# SimulatorT1-T2-AdapterRevB.net
KiCad netlist of a schematic drawn in EAGLE
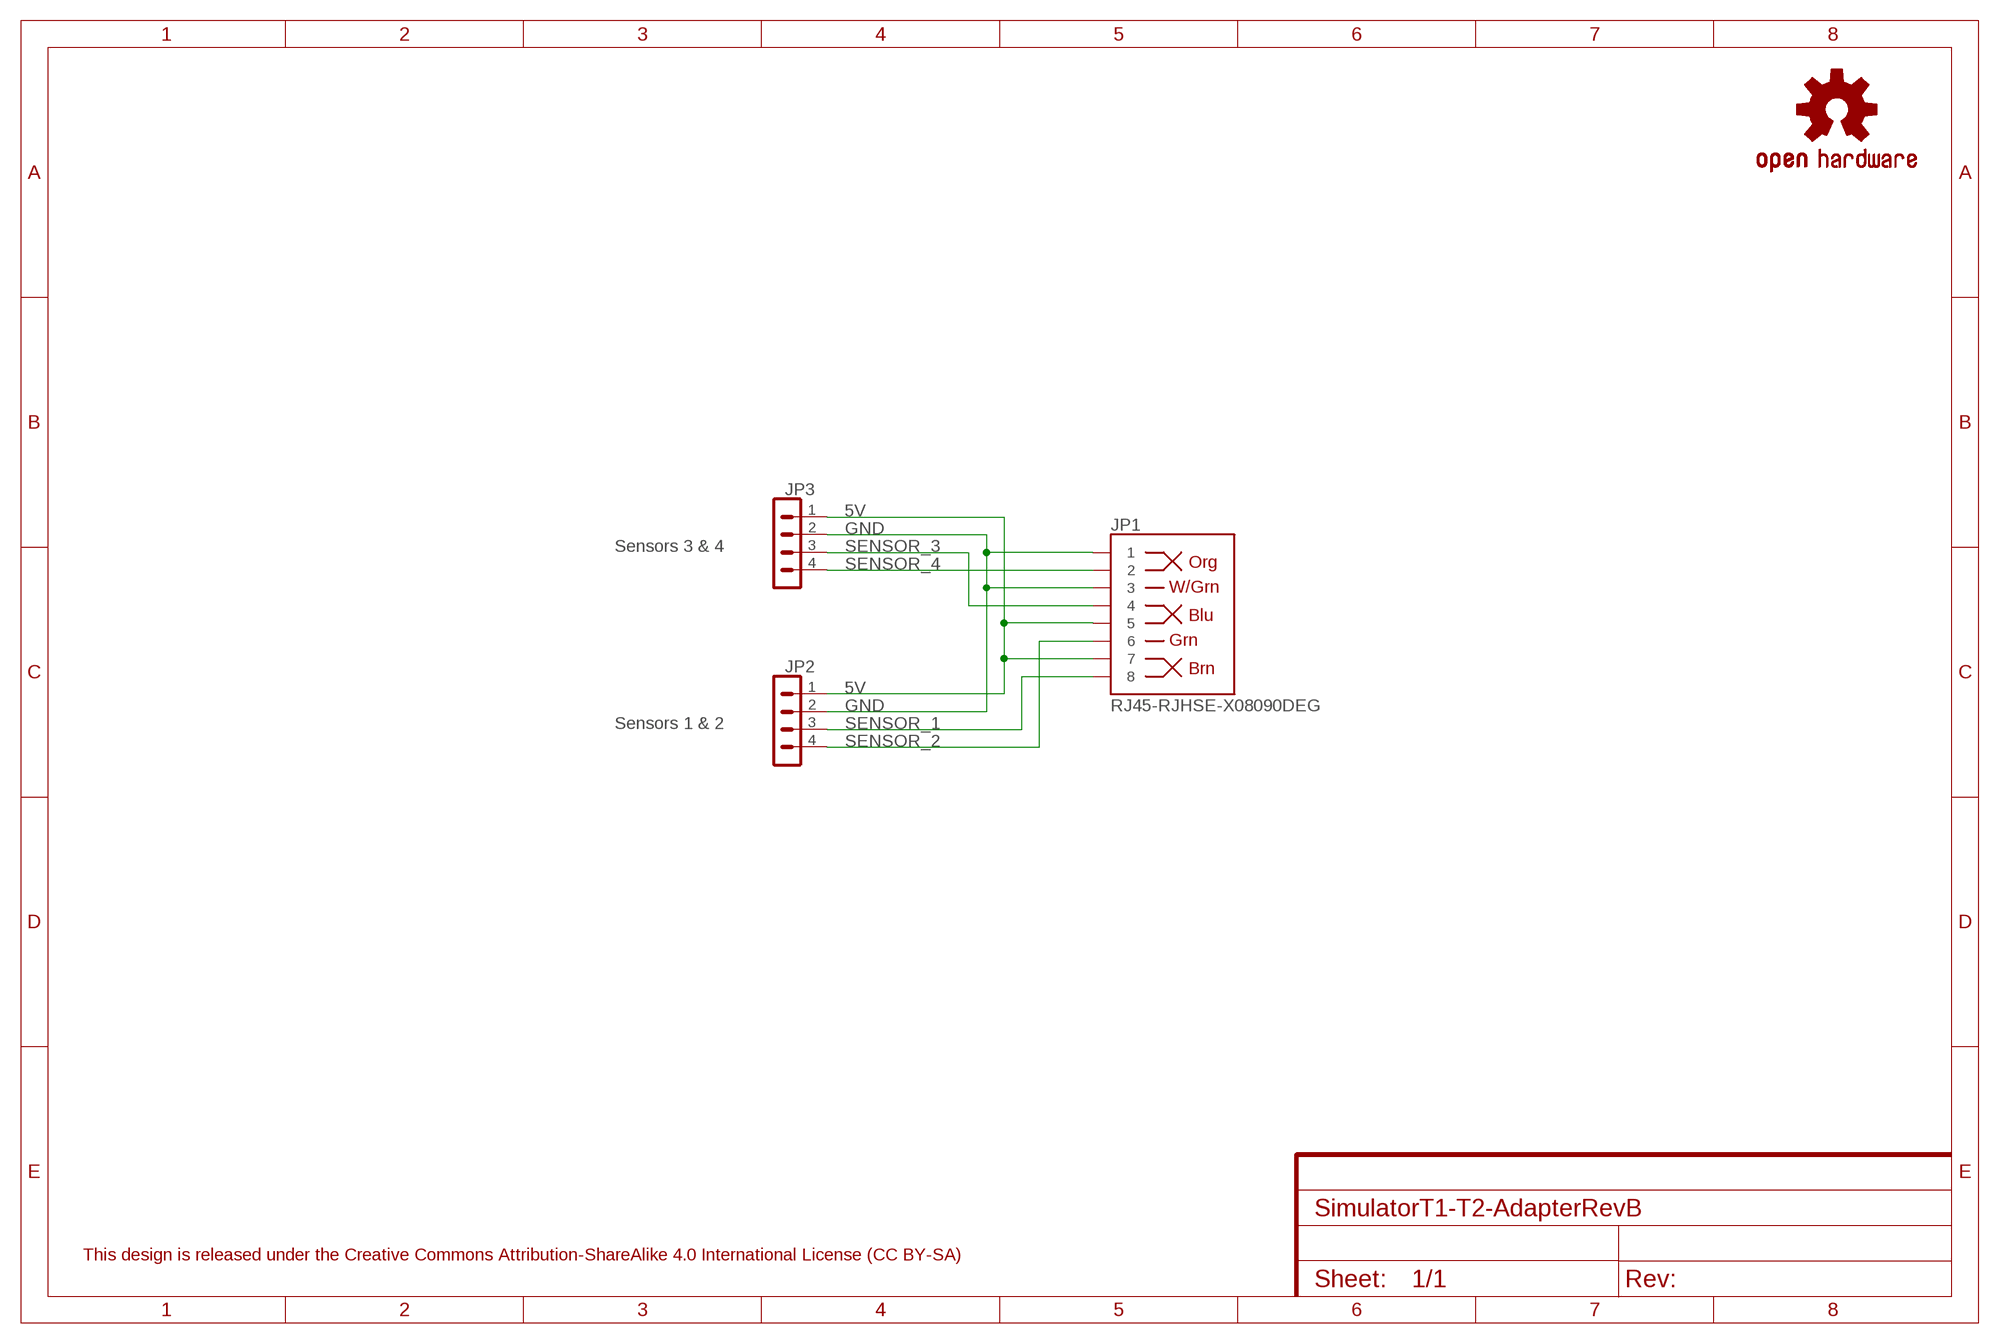
[diagram p0: schematic, sheet 1]

(export (version "E")
  (design (tool "Eeschema 10.0.6"))
  (components
    (comp (ref "JP1")
      (value "RJ45-RJHSE-X08090DEG")
      (footprint "eagle-import:RJ45-RJHSE-5080")
      (libsource (lib "eagle-import") (part "RJ45-RJHSE-X08090DEG"))
    )
    (comp (ref "JP2")
      (value "MOLEX_KK_254_4WAY")
      (footprint "eagle-import:MOLEX_KK_254_4WAY")
      (libsource (lib "eagle-import") (part "MOLEX_KK_254_4WAY"))
    )
    (comp (ref "JP3")
      (value "MOLEX_KK_254_4WAY")
      (footprint "eagle-import:MOLEX_KK_254_4WAY")
      (libsource (lib "eagle-import") (part "MOLEX_KK_254_4WAY"))
    )
    (comp (ref "LOGO1")
      (value "OSHW-LOGOS")
      (footprint "eagle-import:OSHW-LOGO-S")
      (libsource (lib "eagle-import") (part "OSHW-LOGOS"))
    )
  )
  (nets
    (net (code "1") (name "/5V") (class "Default")
      (node (ref "JP1") (pin "5") (pinfunction "5_5") (pintype "bidirectional"))
      (node (ref "JP1") (pin "7") (pinfunction "7_7") (pintype "bidirectional"))
      (node (ref "JP2") (pin "1") (pinfunction "1_1") (pintype "passive"))
      (node (ref "JP3") (pin "1") (pinfunction "1_1") (pintype "passive"))
    )
    (net (code "2") (name "/GND") (class "Default")
      (node (ref "JP1") (pin "1") (pinfunction "1_1") (pintype "bidirectional"))
      (node (ref "JP1") (pin "3") (pinfunction "3_3") (pintype "bidirectional"))
      (node (ref "JP2") (pin "2") (pinfunction "2_2") (pintype "passive"))
      (node (ref "JP3") (pin "2") (pinfunction "2_2") (pintype "passive"))
    )
    (net (code "3") (name "/SENSOR_1") (class "Default")
      (node (ref "JP1") (pin "8") (pinfunction "8_8") (pintype "bidirectional"))
      (node (ref "JP2") (pin "3") (pinfunction "3_3") (pintype "passive"))
    )
    (net (code "4") (name "/SENSOR_2") (class "Default")
      (node (ref "JP1") (pin "6") (pinfunction "6_6") (pintype "bidirectional"))
      (node (ref "JP2") (pin "4") (pinfunction "4_4") (pintype "passive"))
    )
    (net (code "5") (name "/SENSOR_3") (class "Default")
      (node (ref "JP1") (pin "4") (pinfunction "4_4") (pintype "bidirectional"))
      (node (ref "JP3") (pin "3") (pinfunction "3_3") (pintype "passive"))
    )
    (net (code "6") (name "/SENSOR_4") (class "Default")
      (node (ref "JP1") (pin "2") (pinfunction "2_2") (pintype "bidirectional"))
      (node (ref "JP3") (pin "4") (pinfunction "4_4") (pintype "passive"))
    )
  )
)
